# MCU.net
KiCad netlist of a schematic drawn in Altium Designer
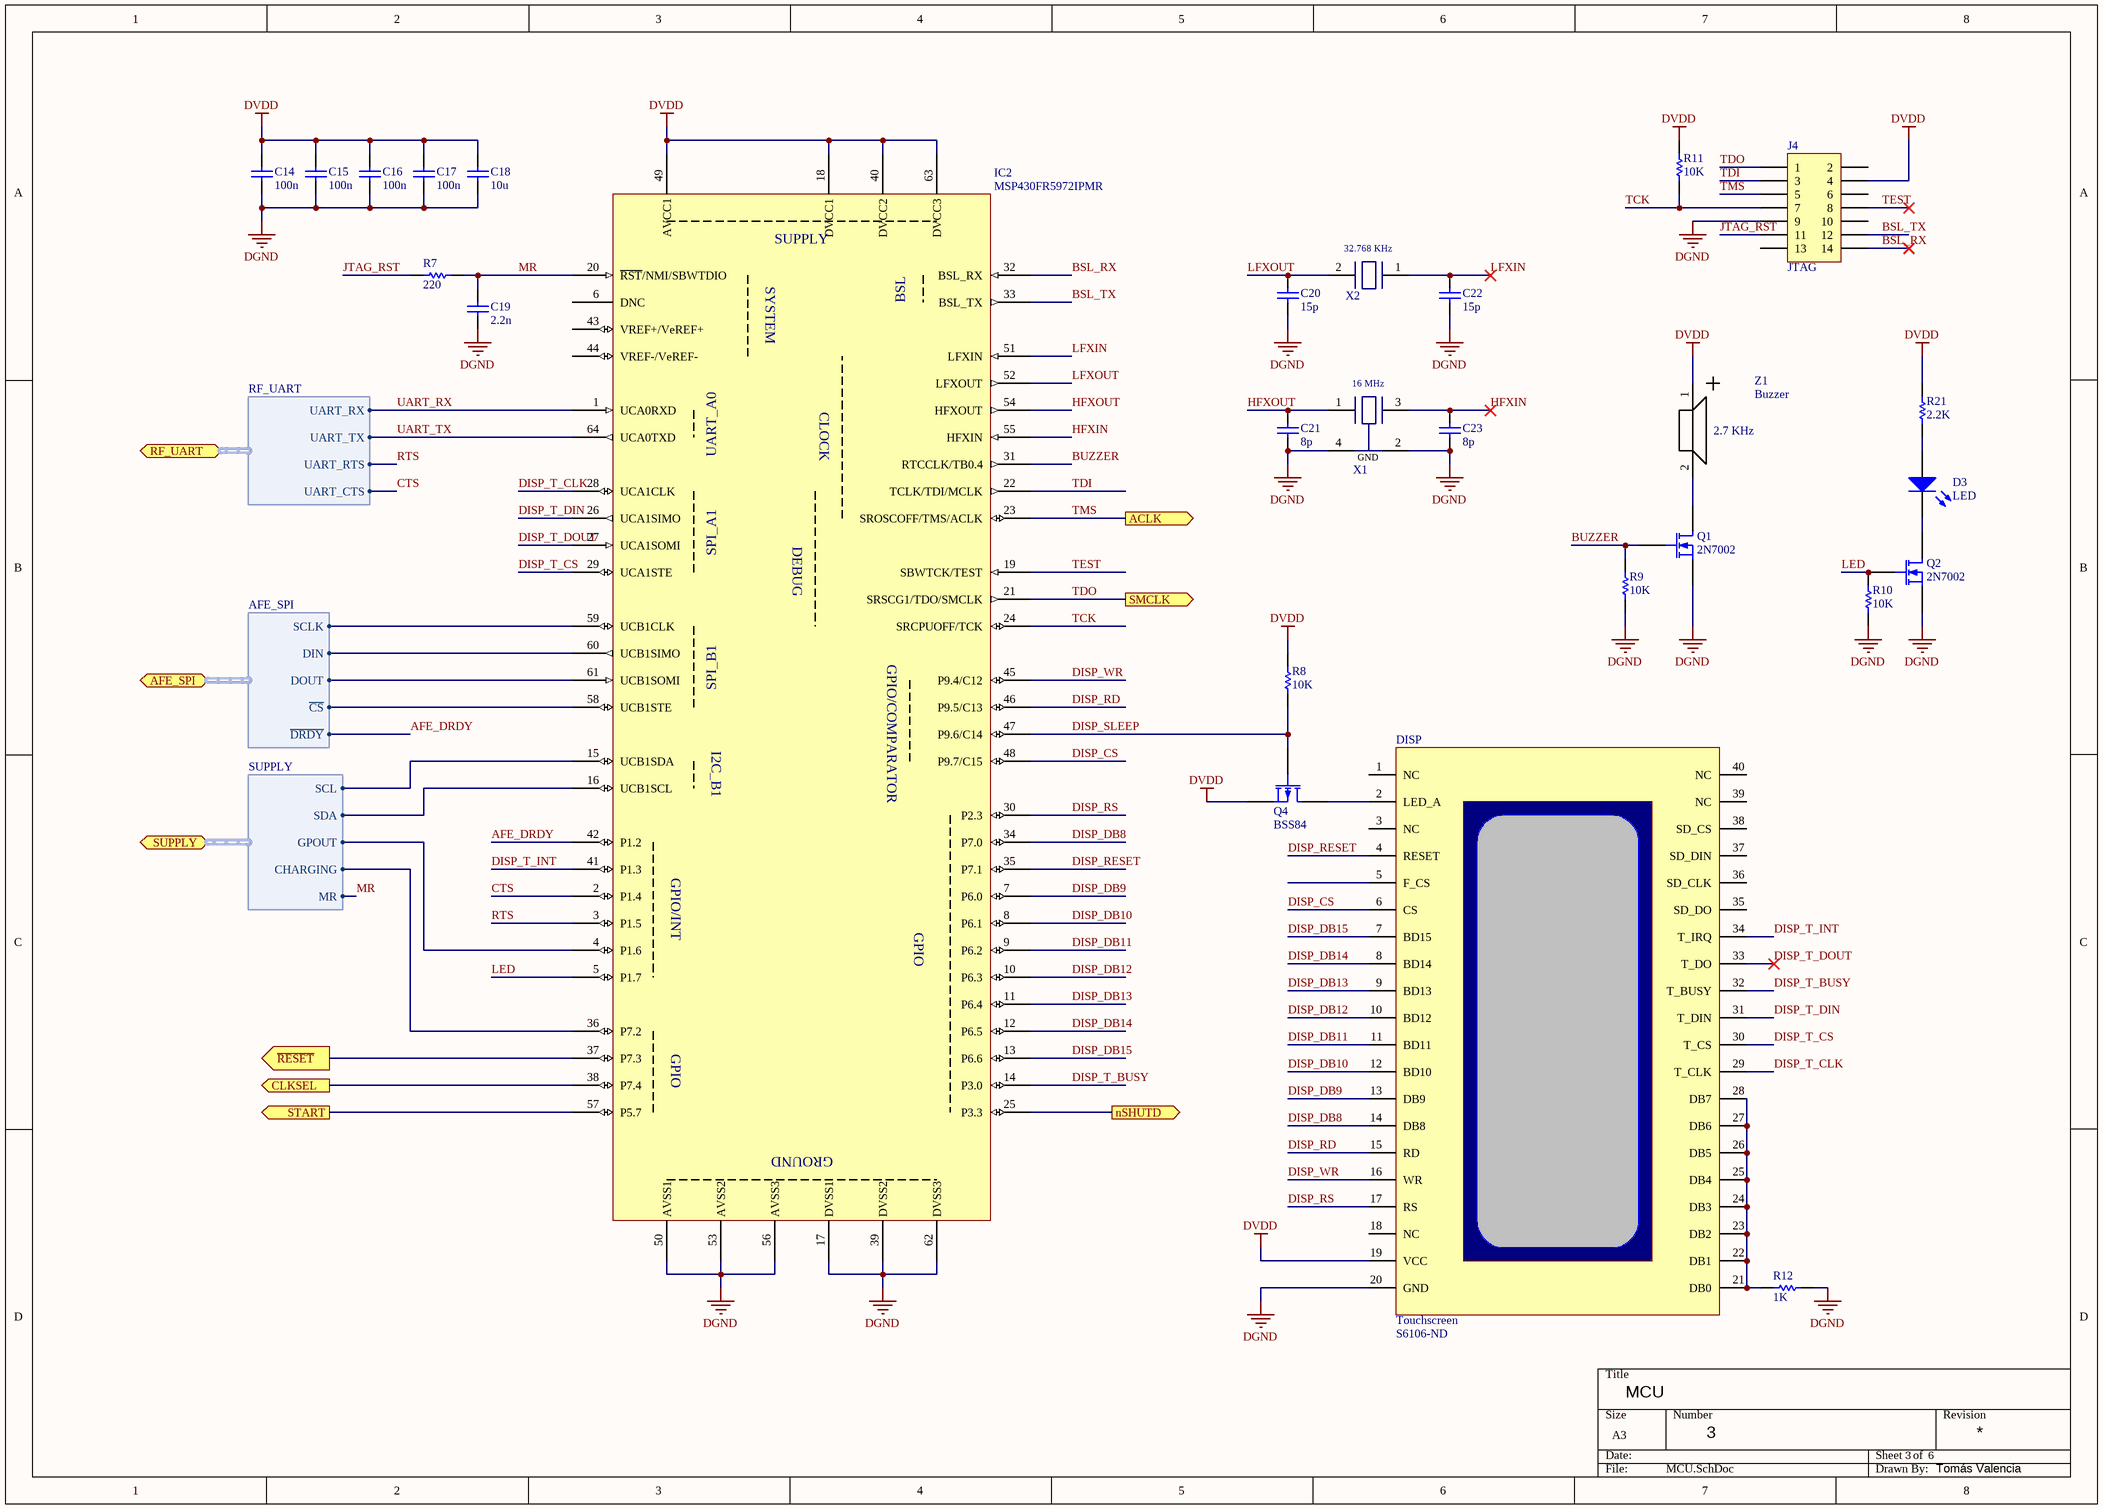
[diagram p0: MCU.SchDoc]

(export (version "E")
  (design (tool "Eeschema 10.0.6"))
  (components
    (comp (ref "C14")
      (value "100n")
      (footprint "C0603")
      (description "Capacitor")
      (libsource (lib "Common Devices") (part "Capacitor"))
    )
    (comp (ref "C15")
      (value "100n")
      (footprint "C0603")
      (description "Capacitor")
      (libsource (lib "Common Devices") (part "Capacitor"))
    )
    (comp (ref "C16")
      (value "100n")
      (footprint "C0603")
      (description "Capacitor")
      (libsource (lib "Common Devices") (part "Capacitor"))
    )
    (comp (ref "C17")
      (value "100n")
      (footprint "C0603")
      (description "Capacitor")
      (libsource (lib "Common Devices") (part "Capacitor"))
    )
    (comp (ref "C18")
      (value "10u")
      (footprint "C0603")
      (description "Capacitor")
      (libsource (lib "Common Devices") (part "Capacitor"))
    )
    (comp (ref "C19")
      (value "2.2n")
      (footprint "C0603")
      (description "Capacitor")
      (libsource (lib "Common Devices") (part "Capacitor"))
    )
    (comp (ref "C20")
      (value "15p")
      (footprint "C0603")
      (description "Capacitor")
      (libsource (lib "Common Devices") (part "Capacitor"))
    )
    (comp (ref "C21")
      (value "8p")
      (footprint "C0603")
      (description "Capacitor")
      (libsource (lib "Common Devices") (part "Capacitor"))
    )
    (comp (ref "C22")
      (value "15p")
      (footprint "C0603")
      (description "Capacitor")
      (libsource (lib "Common Devices") (part "Capacitor"))
    )
    (comp (ref "C23")
      (value "8p")
      (footprint "C0603")
      (description "Capacitor")
      (libsource (lib "Common Devices") (part "Capacitor"))
    )
    (comp (ref "D3") (value "LED") (footprint "LED3015M") (libsource (lib "Common Devices") (part "LED")))
    (comp (ref "DISP")
      (value "Touchscreen")
      (footprint "TSCREEN_CONN")
      (fields (field (name "SUPPLIER PART NUMBER 1") "S6106-ND"))
      (libsource (lib "Main Board") (part "Touchscreen"))
    )
    (comp (ref "IC2")
      (value "MSP430FR5972IPMR")
      (footprint "MSP430FR5972")
      (libsource (lib "Main Board") (part "MSP430FR5972IPMR"))
    )
    (comp (ref "J4")
      (value "JTAG")
      (footprint "JTAG 14 PINS")
      (description "JTAG 7X2 Pin Header 90º")
      (libsource (lib "Main Board") (part "JTAG 14 Pins"))
    )
    (comp (ref "Q1")
      (value "2N7002")
      (footprint "SOT65P210X110-3N")
      (description "Transistor, MOSFET, N-Channel, 60V, 300mA")
      (libsource (lib "Common Devices") (part "2N7002"))
    )
    (comp (ref "Q2")
      (value "2N7002")
      (footprint "SOT65P210X110-3N")
      (description "Transistor, MOSFET, N-Channel, 60V, 300mA")
      (libsource (lib "Common Devices") (part "2N7002"))
    )
    (comp (ref "Q4")
      (value "BSS84")
      (footprint "SOT65P210X110-3N")
      (description "Transistor, MOSFET, P-Channel, 60V, 300mA")
      (libsource (lib "Common Devices") (part "BSS84"))
    )
    (comp (ref "R7")
      (value "220")
      (footprint "R0603")
      (description "Resistor")
      (libsource (lib "Common Devices") (part "Resistor"))
    )
    (comp (ref "R8")
      (value "10K")
      (footprint "R0603")
      (description "Resistor")
      (libsource (lib "Common Devices") (part "Resistor"))
    )
    (comp (ref "R9")
      (value "10K")
      (footprint "R0603")
      (description "Resistor")
      (libsource (lib "Common Devices") (part "Resistor"))
    )
    (comp (ref "R10")
      (value "10K")
      (footprint "R0603")
      (description "Resistor")
      (libsource (lib "Common Devices") (part "Resistor"))
    )
    (comp (ref "R11")
      (value "10K")
      (footprint "R0603")
      (description "Resistor")
      (libsource (lib "Common Devices") (part "Resistor"))
    )
    (comp (ref "R12")
      (value "1K")
      (footprint "R0603")
      (description "Resistor")
      (libsource (lib "Common Devices") (part "Resistor"))
    )
    (comp (ref "R21")
      (value "2.2K")
      (footprint "R0603")
      (description "Resistor")
      (libsource (lib "Common Devices") (part "Resistor"))
    )
    (comp (ref "X1")
      (value "XTAL_16MHZ")
      (footprint "XTAL_16_MHz")
      (libsource (lib "Main Board") (part "XTAL_16_MHz"))
    )
    (comp (ref "X2")
      (value "XTAL_32768")
      (footprint "xtal_32768")
      (libsource (lib "Main Board") (part "XTAL_32768"))
    )
    (comp (ref "Z1")
      (value "Buzzer")
      (footprint "KSSG74B16")
      (description "Magnetic Buzzer 2.7 KHz")
      (libsource (lib "Main Board") (part "Buzzer"))
    )
  )
  (nets
    (net (code "4") (name "/AFE_DRDY") (class "Default")
      (node (ref "IC2") (pin "42") (pinfunction "P1.2_42") (pintype "bidirectional"))
    )
    (net (code "5") (name "/BSL_RX") (class "Default")
      (node (ref "IC2") (pin "32") (pinfunction "BSL_RX_32") (pintype "input"))
      (node (ref "J4") (pin "14") (pinfunction "14_14") (pintype "passive"))
    )
    (net (code "6") (name "/BSL_TX") (class "Default")
      (node (ref "IC2") (pin "33") (pinfunction "BSL_TX_33") (pintype "output"))
      (node (ref "J4") (pin "12") (pinfunction "12_12") (pintype "passive"))
    )
    (net (code "7") (name "/BUZZER") (class "Default")
      (node (ref "IC2") (pin "31") (pinfunction "RTCCLK/TB0.4_31") (pintype "output"))
      (node (ref "Q1") (pin "1") (pinfunction "G_1") (pintype "passive"))
      (node (ref "R9") (pin "2") (pinfunction "2_2") (pintype "passive"))
    )
    (net (code "8") (name "/CHARGING") (class "Default")
      (node (ref "IC2") (pin "36") (pinfunction "P7.2_36") (pintype "bidirectional"))
    )
    (net (code "9") (name "/CLKSEL") (class "Default")
      (node (ref "IC2") (pin "38") (pinfunction "P7.4_38") (pintype "bidirectional"))
    )
    (net (code "10") (name "/CTS") (class "Default")
      (node (ref "IC2") (pin "2") (pinfunction "P1.4_2") (pintype "bidirectional"))
    )
    (net (code "11") (name "/DIN") (class "Default")
      (node (ref "IC2") (pin "60") (pinfunction "UCB1SIMO_60") (pintype "output"))
    )
    (net (code "12") (name "/DISP_CS") (class "Default")
      (node (ref "DISP") (pin "6") (pinfunction "CS_6") (pintype "passive"))
      (node (ref "IC2") (pin "48") (pinfunction "P9.7/C15_48") (pintype "bidirectional"))
    )
    (net (code "13") (name "/DISP_DB8") (class "Default")
      (node (ref "DISP") (pin "14") (pinfunction "DB8_14") (pintype "passive"))
      (node (ref "IC2") (pin "34") (pinfunction "P7.0_34") (pintype "bidirectional"))
    )
    (net (code "14") (name "/DISP_DB9") (class "Default")
      (node (ref "DISP") (pin "13") (pinfunction "DB9_13") (pintype "passive"))
      (node (ref "IC2") (pin "7") (pinfunction "P6.0_7") (pintype "bidirectional"))
    )
    (net (code "15") (name "/DISP_DB10") (class "Default")
      (node (ref "DISP") (pin "12") (pinfunction "BD10_12") (pintype "passive"))
      (node (ref "IC2") (pin "8") (pinfunction "P6.1_8") (pintype "bidirectional"))
    )
    (net (code "16") (name "/DISP_DB11") (class "Default")
      (node (ref "DISP") (pin "11") (pinfunction "BD11_11") (pintype "passive"))
      (node (ref "IC2") (pin "9") (pinfunction "P6.2_9") (pintype "bidirectional"))
    )
    (net (code "17") (name "/DISP_DB12") (class "Default")
      (node (ref "DISP") (pin "10") (pinfunction "BD12_10") (pintype "passive"))
      (node (ref "IC2") (pin "10") (pinfunction "P6.3_10") (pintype "bidirectional"))
    )
    (net (code "18") (name "/DISP_DB13") (class "Default")
      (node (ref "DISP") (pin "9") (pinfunction "BD13_9") (pintype "passive"))
      (node (ref "IC2") (pin "11") (pinfunction "P6.4_11") (pintype "bidirectional"))
    )
    (net (code "19") (name "/DISP_DB14") (class "Default")
      (node (ref "DISP") (pin "8") (pinfunction "BD14_8") (pintype "passive"))
      (node (ref "IC2") (pin "12") (pinfunction "P6.5_12") (pintype "bidirectional"))
    )
    (net (code "20") (name "/DISP_DB15") (class "Default")
      (node (ref "DISP") (pin "7") (pinfunction "BD15_7") (pintype "passive"))
      (node (ref "IC2") (pin "13") (pinfunction "P6.6_13") (pintype "bidirectional"))
    )
    (net (code "21") (name "/DISP_RD") (class "Default")
      (node (ref "DISP") (pin "15") (pinfunction "RD_15") (pintype "passive"))
      (node (ref "IC2") (pin "46") (pinfunction "P9.5/C13_46") (pintype "bidirectional"))
    )
    (net (code "22") (name "/DISP_RESET") (class "Default")
      (node (ref "DISP") (pin "4") (pinfunction "RESET_4") (pintype "passive"))
      (node (ref "IC2") (pin "35") (pinfunction "P7.1_35") (pintype "bidirectional"))
    )
    (net (code "23") (name "/DISP_RS") (class "Default")
      (node (ref "DISP") (pin "17") (pinfunction "RS_17") (pintype "passive"))
      (node (ref "IC2") (pin "30") (pinfunction "P2.3_30") (pintype "bidirectional"))
    )
    (net (code "24") (name "/DISP_SLEEP") (class "Default")
      (node (ref "IC2") (pin "47") (pinfunction "P9.6/C14_47") (pintype "bidirectional"))
      (node (ref "Q4") (pin "1") (pinfunction "G_1") (pintype "passive"))
      (node (ref "R8") (pin "1") (pinfunction "1_1") (pintype "passive"))
    )
    (net (code "25") (name "/DISP_T_BUSY") (class "Default")
      (node (ref "DISP") (pin "32") (pinfunction "T_BUSY_32") (pintype "passive"))
      (node (ref "IC2") (pin "14") (pinfunction "P3.0_14") (pintype "bidirectional"))
    )
    (net (code "26") (name "/DISP_T_CLK") (class "Default")
      (node (ref "DISP") (pin "29") (pinfunction "T_CLK_29") (pintype "passive"))
      (node (ref "IC2") (pin "28") (pinfunction "UCA1CLK_28") (pintype "bidirectional"))
    )
    (net (code "27") (name "/DISP_T_CS") (class "Default")
      (node (ref "DISP") (pin "30") (pinfunction "T_CS_30") (pintype "passive"))
      (node (ref "IC2") (pin "29") (pinfunction "UCA1STE_29") (pintype "bidirectional"))
    )
    (net (code "28") (name "/DISP_T_DIN") (class "Default")
      (node (ref "DISP") (pin "31") (pinfunction "T_DIN_31") (pintype "passive"))
      (node (ref "IC2") (pin "26") (pinfunction "UCA1SIMO_26") (pintype "output"))
    )
    (net (code "29") (name "/DISP_T_DOUT") (class "Default")
      (node (ref "DISP") (pin "33") (pinfunction "T_DO_33") (pintype "passive"))
      (node (ref "IC2") (pin "27") (pinfunction "UCA1SOMI_27") (pintype "input"))
    )
    (net (code "30") (name "/DISP_T_INT") (class "Default")
      (node (ref "DISP") (pin "34") (pinfunction "T_IRQ_34") (pintype "passive"))
      (node (ref "IC2") (pin "41") (pinfunction "P1.3_41") (pintype "bidirectional"))
    )
    (net (code "31") (name "/DISP_WR") (class "Default")
      (node (ref "DISP") (pin "16") (pinfunction "WR_16") (pintype "passive"))
      (node (ref "IC2") (pin "45") (pinfunction "P9.4/C12_45") (pintype "bidirectional"))
    )
    (net (code "32") (name "/DOUT") (class "Default")
      (node (ref "IC2") (pin "61") (pinfunction "UCB1SOMI_61") (pintype "input"))
    )
    (net (code "33") (name "/GPOUT") (class "Default")
      (node (ref "IC2") (pin "4") (pinfunction "P1.6_4") (pintype "bidirectional"))
    )
    (net (code "34") (name "/HFXIN") (class "Default")
      (node (ref "C23") (pin "2") (pinfunction "2_2") (pintype "passive"))
      (node (ref "IC2") (pin "55") (pinfunction "HFXIN_55") (pintype "input"))
      (node (ref "X1") (pin "3") (pinfunction "IN_3") (pintype "passive"))
    )
    (net (code "35") (name "/HFXOUT") (class "Default")
      (node (ref "C21") (pin "2") (pinfunction "2_2") (pintype "passive"))
      (node (ref "IC2") (pin "54") (pinfunction "HFXOUT_54") (pintype "output"))
      (node (ref "X1") (pin "1") (pinfunction "OUT_1") (pintype "passive"))
    )
    (net (code "36") (name "/JTAG_RST") (class "Default")
      (node (ref "J4") (pin "11") (pinfunction "11_11") (pintype "passive"))
      (node (ref "R7") (pin "1") (pinfunction "1_1") (pintype "passive"))
    )
    (net (code "37") (name "/LED") (class "Default")
      (node (ref "IC2") (pin "5") (pinfunction "P1.7_5") (pintype "bidirectional"))
      (node (ref "Q2") (pin "1") (pinfunction "G_1") (pintype "passive"))
      (node (ref "R10") (pin "2") (pinfunction "2_2") (pintype "passive"))
    )
    (net (code "38") (name "/LFXIN") (class "Default")
      (node (ref "C22") (pin "1") (pinfunction "1_1") (pintype "passive"))
      (node (ref "IC2") (pin "51") (pinfunction "LFXIN_51") (pintype "input"))
      (node (ref "X2") (pin "1") (pinfunction "IN_1") (pintype "passive"))
    )
    (net (code "39") (name "/LFXOUT") (class "Default")
      (node (ref "C20") (pin "1") (pinfunction "1_1") (pintype "passive"))
      (node (ref "IC2") (pin "52") (pinfunction "LFXOUT_52") (pintype "output"))
      (node (ref "X2") (pin "2") (pinfunction "OUT_2") (pintype "passive"))
    )
    (net (code "40") (name "/MR") (class "Default")
      (node (ref "C19") (pin "2") (pinfunction "2_2") (pintype "passive"))
      (node (ref "IC2") (pin "20") (pinfunction "~{RST}/NMI/SBWTDIO_20") (pintype "input"))
      (node (ref "R7") (pin "2") (pinfunction "2_2") (pintype "passive"))
    )
    (net (code "41") (name "/RTS") (class "Default")
      (node (ref "IC2") (pin "3") (pinfunction "P1.5_3") (pintype "bidirectional"))
    )
    (net (code "42") (name "/SCL") (class "Default")
      (node (ref "IC2") (pin "15") (pinfunction "UCB1SDA_15") (pintype "bidirectional"))
    )
    (net (code "43") (name "/SCLK") (class "Default")
      (node (ref "IC2") (pin "59") (pinfunction "UCB1CLK_59") (pintype "bidirectional"))
    )
    (net (code "44") (name "/SDA") (class "Default")
      (node (ref "IC2") (pin "16") (pinfunction "UCB1SCL_16") (pintype "bidirectional"))
    )
    (net (code "45") (name "/START") (class "Default")
      (node (ref "IC2") (pin "57") (pinfunction "P5.7_57") (pintype "bidirectional"))
    )
    (net (code "46") (name "/TCK") (class "Default")
      (node (ref "IC2") (pin "24") (pinfunction "SRCPUOFF/TCK_24") (pintype "bidirectional"))
      (node (ref "J4") (pin "7") (pinfunction "7_7") (pintype "passive"))
      (node (ref "R11") (pin "1") (pinfunction "1_1") (pintype "passive"))
    )
    (net (code "47") (name "/TDI") (class "Default")
      (node (ref "IC2") (pin "22") (pinfunction "TCLK/TDI/MCLK_22") (pintype "output"))
      (node (ref "J4") (pin "3") (pinfunction "3_3") (pintype "passive"))
    )
    (net (code "48") (name "/TDO") (class "Default")
      (node (ref "IC2") (pin "21") (pinfunction "SRSCG1/TDO/SMCLK_21") (pintype "output"))
      (node (ref "J4") (pin "1") (pinfunction "1_1") (pintype "passive"))
    )
    (net (code "49") (name "/TEST") (class "Default")
      (node (ref "IC2") (pin "19") (pinfunction "SBWTCK/TEST_19") (pintype "input"))
      (node (ref "J4") (pin "8") (pinfunction "8_8") (pintype "passive"))
    )
    (net (code "50") (name "/TMS") (class "Default")
      (node (ref "IC2") (pin "23") (pinfunction "SROSCOFF/TMS/ACLK_23") (pintype "bidirectional"))
      (node (ref "J4") (pin "5") (pinfunction "5_5") (pintype "passive"))
    )
    (net (code "51") (name "/UART_RX") (class "Default")
      (node (ref "IC2") (pin "1") (pinfunction "UCA0RXD_1") (pintype "input"))
    )
    (net (code "52") (name "/UART_TX") (class "Default")
      (node (ref "IC2") (pin "64") (pinfunction "UCA0TXD_64") (pintype "output"))
    )
    (net (code "53") (name "/nSHUTD") (class "Default")
      (node (ref "IC2") (pin "25") (pinfunction "P3.3_25") (pintype "bidirectional"))
    )
    (net (code "57") (name "/~{CS}") (class "Default")
      (node (ref "IC2") (pin "58") (pinfunction "UCB1STE_58") (pintype "bidirectional"))
    )
    (net (code "58") (name "/~{RESET}") (class "Default")
      (node (ref "IC2") (pin "37") (pinfunction "P7.3_37") (pintype "bidirectional"))
    )
    (net (code "59") (name "DGND") (class "Default")
      (node (ref "C14") (pin "1") (pinfunction "1_1") (pintype "passive"))
      (node (ref "C15") (pin "1") (pinfunction "1_1") (pintype "passive"))
      (node (ref "C16") (pin "1") (pinfunction "1_1") (pintype "passive"))
      (node (ref "C17") (pin "1") (pinfunction "1_1") (pintype "passive"))
      (node (ref "C18") (pin "1") (pinfunction "1_1") (pintype "passive"))
      (node (ref "C19") (pin "1") (pinfunction "1_1") (pintype "passive"))
      (node (ref "C20") (pin "2") (pinfunction "2_2") (pintype "passive"))
      (node (ref "C21") (pin "1") (pinfunction "1_1") (pintype "passive"))
      (node (ref "C22") (pin "2") (pinfunction "2_2") (pintype "passive"))
      (node (ref "C23") (pin "1") (pinfunction "1_1") (pintype "passive"))
      (node (ref "DISP") (pin "20") (pinfunction "GND_20") (pintype "passive"))
      (node (ref "IC2") (pin "17") (pinfunction "DVSS1_17") (pintype "power_in"))
      (node (ref "IC2") (pin "39") (pinfunction "DVSS2_39") (pintype "power_in"))
      (node (ref "IC2") (pin "50") (pinfunction "AVSS1_50") (pintype "passive"))
      (node (ref "IC2") (pin "53") (pinfunction "AVSS2_53") (pintype "passive"))
      (node (ref "IC2") (pin "56") (pinfunction "AVSS3_56") (pintype "passive"))
      (node (ref "IC2") (pin "62") (pinfunction "DVSS3_62") (pintype "power_in"))
      (node (ref "J4") (pin "9") (pinfunction "9_9") (pintype "passive"))
      (node (ref "Q1") (pin "2") (pinfunction "S_2") (pintype "passive"))
      (node (ref "Q2") (pin "2") (pinfunction "S_2") (pintype "passive"))
      (node (ref "R10") (pin "1") (pinfunction "1_1") (pintype "passive"))
      (node (ref "R12") (pin "2") (pinfunction "2_2") (pintype "passive"))
      (node (ref "R9") (pin "1") (pinfunction "1_1") (pintype "passive"))
      (node (ref "X1") (pin "2") (pinfunction "GND_2") (pintype "passive"))
      (node (ref "X1") (pin "4") (pinfunction "GND_4") (pintype "passive"))
    )
    (net (code "60") (name "DVDD") (class "Default")
      (node (ref "C14") (pin "2") (pinfunction "2_2") (pintype "passive"))
      (node (ref "C15") (pin "2") (pinfunction "2_2") (pintype "passive"))
      (node (ref "C16") (pin "2") (pinfunction "2_2") (pintype "passive"))
      (node (ref "C17") (pin "2") (pinfunction "2_2") (pintype "passive"))
      (node (ref "C18") (pin "2") (pinfunction "2_2") (pintype "passive"))
      (node (ref "DISP") (pin "19") (pinfunction "VCC_19") (pintype "passive"))
      (node (ref "IC2") (pin "18") (pinfunction "DVCC1_18") (pintype "power_in"))
      (node (ref "IC2") (pin "40") (pinfunction "DVCC2_40") (pintype "power_in"))
      (node (ref "IC2") (pin "49") (pinfunction "AVCC1_49") (pintype "power_in"))
      (node (ref "IC2") (pin "63") (pinfunction "DVCC3_63") (pintype "power_in"))
      (node (ref "J4") (pin "4") (pinfunction "4_4") (pintype "passive"))
      (node (ref "Q4") (pin "2") (pinfunction "S_2") (pintype "passive"))
      (node (ref "R11") (pin "2") (pinfunction "2_2") (pintype "passive"))
      (node (ref "R21") (pin "2") (pinfunction "2_2") (pintype "passive"))
      (node (ref "R8") (pin "2") (pinfunction "2_2") (pintype "passive"))
      (node (ref "Z1") (pin "1") (pinfunction "+_1") (pintype "passive"))
    )
    (net (code "61") (name "Net-(D3-A)") (class "Default")
      (node (ref "D3") (pin "1") (pinfunction "A_1") (pintype "passive"))
      (node (ref "R21") (pin "1") (pinfunction "1_1") (pintype "passive"))
    )
    (net (code "62") (name "Net-(D3-K)") (class "Default")
      (node (ref "D3") (pin "2") (pinfunction "K_2") (pintype "passive"))
      (node (ref "Q2") (pin "3") (pinfunction "D_3") (pintype "passive"))
    )
    (net (code "63") (name "Net-(DISP-DB0)") (class "Default")
      (node (ref "DISP") (pin "21") (pinfunction "DB0_21") (pintype "passive"))
      (node (ref "DISP") (pin "22") (pinfunction "DB1_22") (pintype "passive"))
      (node (ref "DISP") (pin "23") (pinfunction "DB2_23") (pintype "passive"))
      (node (ref "DISP") (pin "24") (pinfunction "DB3_24") (pintype "passive"))
      (node (ref "DISP") (pin "25") (pinfunction "DB4_25") (pintype "passive"))
      (node (ref "DISP") (pin "26") (pinfunction "DB5_26") (pintype "passive"))
      (node (ref "DISP") (pin "27") (pinfunction "DB6_27") (pintype "passive"))
      (node (ref "DISP") (pin "28") (pinfunction "DB7_28") (pintype "passive"))
      (node (ref "R12") (pin "1") (pinfunction "1_1") (pintype "passive"))
    )
    (net (code "64") (name "Net-(DISP-LED_A)") (class "Default")
      (node (ref "DISP") (pin "2") (pinfunction "LED_A_2") (pintype "passive"))
      (node (ref "Q4") (pin "3") (pinfunction "D_3") (pintype "passive"))
    )
    (net (code "65") (name "Net-(Q1-D)") (class "Default")
      (node (ref "Q1") (pin "3") (pinfunction "D_3") (pintype "passive"))
      (node (ref "Z1") (pin "2") (pinfunction "-_2") (pintype "passive"))
    )
    (net (code "66") (name "unconnected-(DISP-F_CS-Pad5)") (class "Default")
      (node (ref "DISP") (pin "5") (pinfunction "F_CS_5") (pintype "passive"))
    )
    (net (code "67") (name "unconnected-(DISP-NC-Pad1)") (class "Default")
      (node (ref "DISP") (pin "1") (pinfunction "NC_1") (pintype "passive"))
    )
    (net (code "68") (name "unconnected-(DISP-NC-Pad3)") (class "Default")
      (node (ref "DISP") (pin "3") (pinfunction "NC_3") (pintype "passive"))
    )
    (net (code "69") (name "unconnected-(DISP-NC-Pad18)") (class "Default")
      (node (ref "DISP") (pin "18") (pinfunction "NC_18") (pintype "passive"))
    )
    (net (code "70") (name "unconnected-(DISP-NC-Pad39)") (class "Default")
      (node (ref "DISP") (pin "39") (pinfunction "NC_39") (pintype "passive"))
    )
    (net (code "71") (name "unconnected-(DISP-NC-Pad40)") (class "Default")
      (node (ref "DISP") (pin "40") (pinfunction "NC_40") (pintype "passive"))
    )
    (net (code "72") (name "unconnected-(DISP-SD_CLK-Pad36)") (class "Default")
      (node (ref "DISP") (pin "36") (pinfunction "SD_CLK_36") (pintype "passive"))
    )
    (net (code "73") (name "unconnected-(DISP-SD_CS-Pad38)") (class "Default")
      (node (ref "DISP") (pin "38") (pinfunction "SD_CS_38") (pintype "passive"))
    )
    (net (code "74") (name "unconnected-(DISP-SD_DIN-Pad37)") (class "Default")
      (node (ref "DISP") (pin "37") (pinfunction "SD_DIN_37") (pintype "passive"))
    )
    (net (code "75") (name "unconnected-(DISP-SD_DO-Pad35)") (class "Default")
      (node (ref "DISP") (pin "35") (pinfunction "SD_DO_35") (pintype "passive"))
    )
    (net (code "76") (name "unconnected-(IC2-DNC-Pad6)") (class "Default")
      (node (ref "IC2") (pin "6") (pinfunction "DNC_6") (pintype "tri_state"))
    )
    (net (code "77") (name "unconnected-(IC2-VREF+{slash}VeREF+-Pad43)") (class "Default")
      (node (ref "IC2") (pin "43") (pinfunction "VREF+/VeREF+_43") (pintype "bidirectional"))
    )
    (net (code "78") (name "unconnected-(IC2-VREF-{slash}VeREF--Pad44)") (class "Default")
      (node (ref "IC2") (pin "44") (pinfunction "VREF-/VeREF-_44") (pintype "bidirectional"))
    )
    (net (code "79") (name "unconnected-(J4-Pad2)") (class "Default")
      (node (ref "J4") (pin "2") (pinfunction "2_2") (pintype "passive"))
    )
    (net (code "80") (name "unconnected-(J4-Pad6)") (class "Default")
      (node (ref "J4") (pin "6") (pinfunction "6_6") (pintype "passive"))
    )
    (net (code "81") (name "unconnected-(J4-Pad10)") (class "Default")
      (node (ref "J4") (pin "10") (pinfunction "10_10") (pintype "passive"))
    )
    (net (code "82") (name "unconnected-(J4-Pad13)") (class "Default")
      (node (ref "J4") (pin "13") (pinfunction "13_13") (pintype "passive"))
    )
  )
)
